# Decoder_relay_4bit_Compact_REV_0.net
KiCad netlist of a schematic drawn in EAGLE
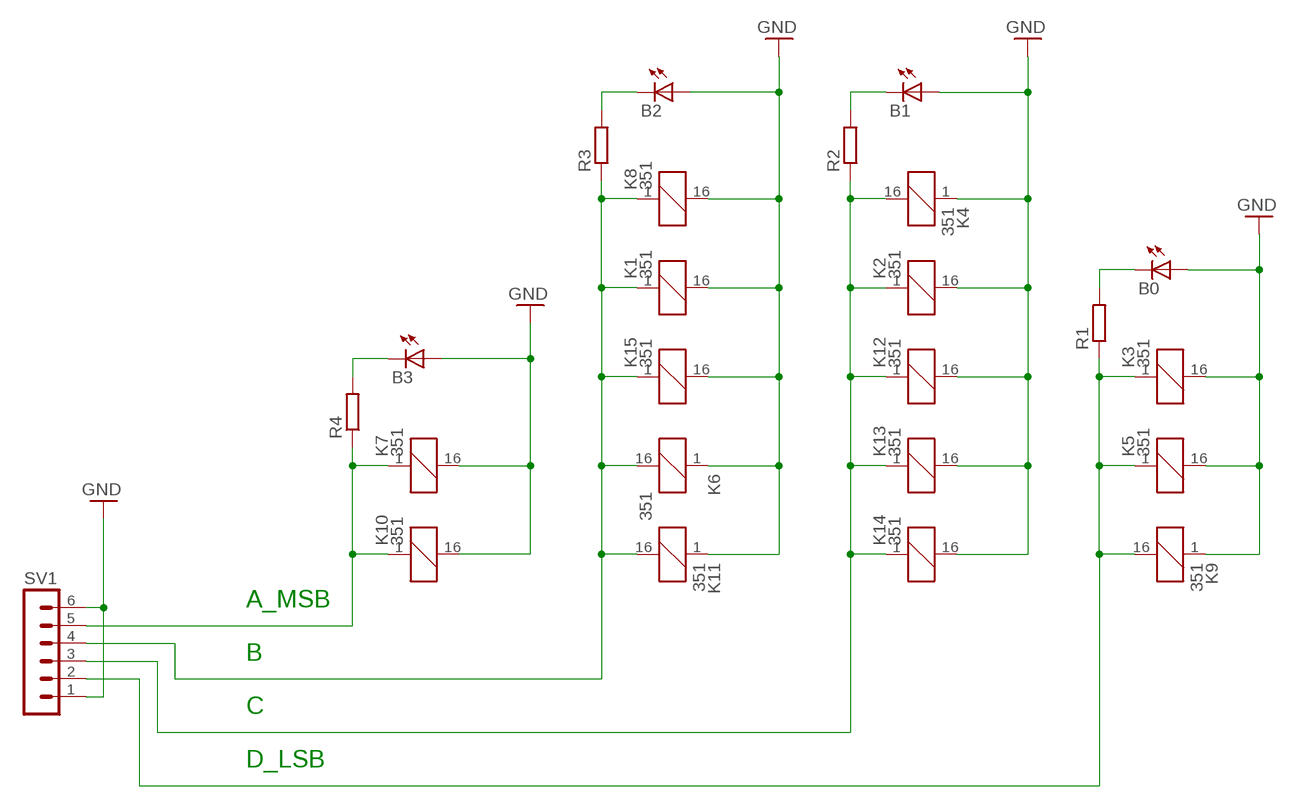
[diagram p0: schematic, sheet 1, part 1 of 2]
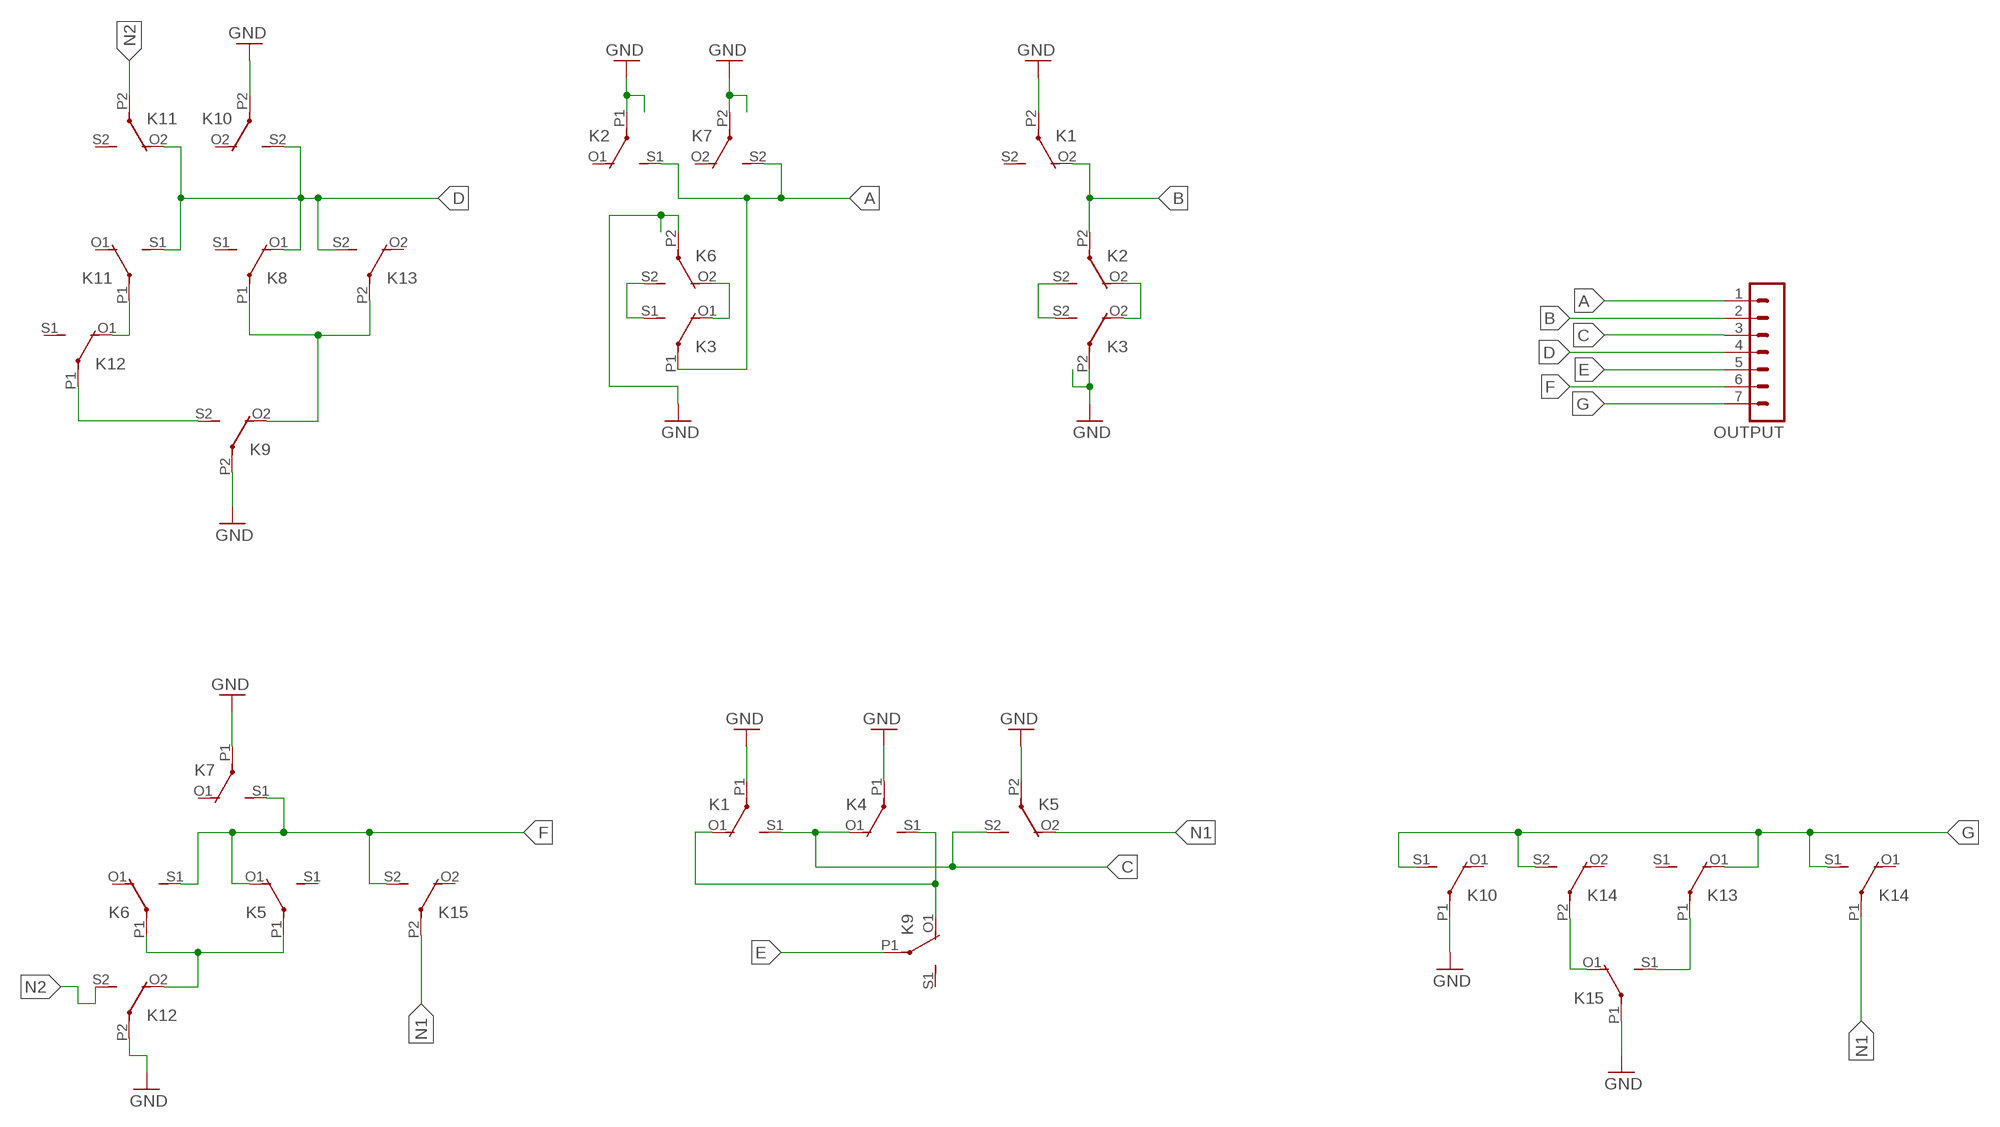
[diagram p1: schematic, sheet 1, part 2 of 2]

(export (version "E")
  (design (tool "Eeschema 10.0.6"))
  (components
    (comp (ref "B0")
      (value "LED3MM")
      (footprint "eagle-import:LED3MM")
      (libsource (lib "eagle-import") (part "LED3MM"))
    )
    (comp (ref "B1")
      (value "LED3MM")
      (footprint "eagle-import:LED3MM")
      (libsource (lib "eagle-import") (part "LED3MM"))
    )
    (comp (ref "B2")
      (value "LED3MM")
      (footprint "eagle-import:LED3MM")
      (libsource (lib "eagle-import") (part "LED3MM"))
    )
    (comp (ref "B3")
      (value "LED3MM")
      (footprint "eagle-import:LED3MM")
      (libsource (lib "eagle-import") (part "LED3MM"))
    )
    (comp (ref "K1")
      (value "351")
      (footprint "eagle-import:351")
      (libsource (lib "eagle-import") (part "351"))
    )
    (comp (ref "K2")
      (value "351")
      (footprint "eagle-import:351")
      (libsource (lib "eagle-import") (part "351"))
    )
    (comp (ref "K3")
      (value "351")
      (footprint "eagle-import:351")
      (libsource (lib "eagle-import") (part "351"))
    )
    (comp (ref "K4")
      (value "351")
      (footprint "eagle-import:351")
      (libsource (lib "eagle-import") (part "351"))
    )
    (comp (ref "K5")
      (value "351")
      (footprint "eagle-import:351")
      (libsource (lib "eagle-import") (part "351"))
    )
    (comp (ref "K6")
      (value "351")
      (footprint "eagle-import:351")
      (libsource (lib "eagle-import") (part "351"))
    )
    (comp (ref "K7")
      (value "351")
      (footprint "eagle-import:351")
      (libsource (lib "eagle-import") (part "351"))
    )
    (comp (ref "K8")
      (value "351")
      (footprint "eagle-import:351")
      (libsource (lib "eagle-import") (part "351"))
    )
    (comp (ref "K9")
      (value "351")
      (footprint "eagle-import:351")
      (libsource (lib "eagle-import") (part "351"))
    )
    (comp (ref "K10")
      (value "351")
      (footprint "eagle-import:351")
      (libsource (lib "eagle-import") (part "351"))
    )
    (comp (ref "K11")
      (value "351")
      (footprint "eagle-import:351")
      (libsource (lib "eagle-import") (part "351"))
    )
    (comp (ref "K12")
      (value "351")
      (footprint "eagle-import:351")
      (libsource (lib "eagle-import") (part "351"))
    )
    (comp (ref "K13")
      (value "351")
      (footprint "eagle-import:351")
      (libsource (lib "eagle-import") (part "351"))
    )
    (comp (ref "K14")
      (value "351")
      (footprint "eagle-import:351")
      (libsource (lib "eagle-import") (part "351"))
    )
    (comp (ref "K15")
      (value "351")
      (footprint "eagle-import:351")
      (libsource (lib "eagle-import") (part "351"))
    )
    (comp (ref "OUTPUT")
      (value "MA07-1")
      (footprint "eagle-import:MA07-1")
      (libsource (lib "eagle-import") (part "MA07-1"))
    )
    (comp (ref "R1")
      (value "R-EU_M0805")
      (footprint "eagle-import:M0805")
      (libsource (lib "eagle-import") (part "R-EU_M0805"))
    )
    (comp (ref "R2")
      (value "R-EU_M0805")
      (footprint "eagle-import:M0805")
      (libsource (lib "eagle-import") (part "R-EU_M0805"))
    )
    (comp (ref "R3")
      (value "R-EU_M0805")
      (footprint "eagle-import:M0805")
      (libsource (lib "eagle-import") (part "R-EU_M0805"))
    )
    (comp (ref "R4")
      (value "R-EU_M0805")
      (footprint "eagle-import:M0805")
      (libsource (lib "eagle-import") (part "R-EU_M0805"))
    )
    (comp (ref "SV1")
      (value "MA06-1")
      (footprint "eagle-import:MA06-1")
      (libsource (lib "eagle-import") (part "MA06-1"))
    )
  )
  (nets
    (net (code "1") (name "A") (class "Default")
      (node (ref "K2") (pin "S1") (pinfunction "S_S1") (pintype "passive"))
      (node (ref "K3") (pin "P1") (pinfunction "P_P1") (pintype "passive"))
      (node (ref "K7") (pin "S2") (pinfunction "S_S2") (pintype "passive"))
      (node (ref "OUTPUT") (pin "1") (pinfunction "1_1") (pintype "passive"))
    )
    (net (code "2") (name "B") (class "Default")
      (node (ref "K1") (pin "O2") (pinfunction "O_O2") (pintype "passive"))
      (node (ref "K2") (pin "P2") (pinfunction "P_P2") (pintype "passive"))
      (node (ref "OUTPUT") (pin "2") (pinfunction "2_2") (pintype "passive"))
    )
    (net (code "3") (name "C") (class "Default")
      (node (ref "K1") (pin "S1") (pinfunction "S_S1") (pintype "passive"))
      (node (ref "K4") (pin "O1") (pinfunction "O_O1") (pintype "passive"))
      (node (ref "K5") (pin "S2") (pinfunction "S_S2") (pintype "passive"))
      (node (ref "OUTPUT") (pin "3") (pinfunction "3_3") (pintype "passive"))
    )
    (net (code "4") (name "D") (class "Default")
      (node (ref "K10") (pin "S2") (pinfunction "S_S2") (pintype "passive"))
      (node (ref "K11") (pin "O2") (pinfunction "O_O2") (pintype "passive"))
      (node (ref "K11") (pin "S1") (pinfunction "S_S1") (pintype "passive"))
      (node (ref "K13") (pin "S2") (pinfunction "S_S2") (pintype "passive"))
      (node (ref "K8") (pin "O1") (pinfunction "O_O1") (pintype "passive"))
      (node (ref "OUTPUT") (pin "4") (pinfunction "4_4") (pintype "passive"))
    )
    (net (code "5") (name "E") (class "Default")
      (node (ref "K9") (pin "P1") (pinfunction "P_P1") (pintype "passive"))
      (node (ref "OUTPUT") (pin "5") (pinfunction "5_5") (pintype "passive"))
    )
    (net (code "6") (name "F") (class "Default")
      (node (ref "K15") (pin "S2") (pinfunction "S_S2") (pintype "passive"))
      (node (ref "K5") (pin "O1") (pinfunction "O_O1") (pintype "passive"))
      (node (ref "K6") (pin "S1") (pinfunction "S_S1") (pintype "passive"))
      (node (ref "K7") (pin "S1") (pinfunction "S_S1") (pintype "passive"))
      (node (ref "OUTPUT") (pin "6") (pinfunction "6_6") (pintype "passive"))
    )
    (net (code "7") (name "G") (class "Default")
      (node (ref "K10") (pin "S1") (pinfunction "S_S1") (pintype "passive"))
      (node (ref "K13") (pin "O1") (pinfunction "O_O1") (pintype "passive"))
      (node (ref "K14") (pin "S1") (pinfunction "S_S1") (pintype "passive"))
      (node (ref "K14") (pin "S2") (pinfunction "S_S2") (pintype "passive"))
      (node (ref "OUTPUT") (pin "7") (pinfunction "7_7") (pintype "passive"))
    )
    (net (code "8") (name "GND") (class "Default")
      (node (ref "B0") (pin "A") (pinfunction "A_A") (pintype "passive"))
      (node (ref "B1") (pin "A") (pinfunction "A_A") (pintype "passive"))
      (node (ref "B2") (pin "A") (pinfunction "A_A") (pintype "passive"))
      (node (ref "B3") (pin "A") (pinfunction "A_A") (pintype "passive"))
      (node (ref "K1") (pin "16") (pinfunction "2_16") (pintype "passive"))
      (node (ref "K1") (pin "P1") (pinfunction "P_P1") (pintype "passive"))
      (node (ref "K1") (pin "P2") (pinfunction "P_P2") (pintype "passive"))
      (node (ref "K10") (pin "16") (pinfunction "2_16") (pintype "passive"))
      (node (ref "K10") (pin "P1") (pinfunction "P_P1") (pintype "passive"))
      (node (ref "K10") (pin "P2") (pinfunction "P_P2") (pintype "passive"))
      (node (ref "K11") (pin "1") (pinfunction "1_1") (pintype "passive"))
      (node (ref "K12") (pin "16") (pinfunction "2_16") (pintype "passive"))
      (node (ref "K12") (pin "P2") (pinfunction "P_P2") (pintype "passive"))
      (node (ref "K13") (pin "16") (pinfunction "2_16") (pintype "passive"))
      (node (ref "K14") (pin "16") (pinfunction "2_16") (pintype "passive"))
      (node (ref "K15") (pin "16") (pinfunction "2_16") (pintype "passive"))
      (node (ref "K15") (pin "P1") (pinfunction "P_P1") (pintype "passive"))
      (node (ref "K2") (pin "16") (pinfunction "2_16") (pintype "passive"))
      (node (ref "K2") (pin "P1") (pinfunction "P_P1") (pintype "passive"))
      (node (ref "K3") (pin "16") (pinfunction "2_16") (pintype "passive"))
      (node (ref "K3") (pin "P2") (pinfunction "P_P2") (pintype "passive"))
      (node (ref "K4") (pin "1") (pinfunction "1_1") (pintype "passive"))
      (node (ref "K4") (pin "P1") (pinfunction "P_P1") (pintype "passive"))
      (node (ref "K5") (pin "16") (pinfunction "2_16") (pintype "passive"))
      (node (ref "K5") (pin "P2") (pinfunction "P_P2") (pintype "passive"))
      (node (ref "K6") (pin "1") (pinfunction "1_1") (pintype "passive"))
      (node (ref "K6") (pin "P2") (pinfunction "P_P2") (pintype "passive"))
      (node (ref "K7") (pin "16") (pinfunction "2_16") (pintype "passive"))
      (node (ref "K7") (pin "P1") (pinfunction "P_P1") (pintype "passive"))
      (node (ref "K7") (pin "P2") (pinfunction "P_P2") (pintype "passive"))
      (node (ref "K8") (pin "16") (pinfunction "2_16") (pintype "passive"))
      (node (ref "K9") (pin "1") (pinfunction "1_1") (pintype "passive"))
      (node (ref "K9") (pin "P2") (pinfunction "P_P2") (pintype "passive"))
      (node (ref "SV1") (pin "1") (pinfunction "1_1") (pintype "passive"))
      (node (ref "SV1") (pin "6") (pinfunction "6_6") (pintype "passive"))
    )
    (net (code "9") (name "N1") (class "Default")
      (node (ref "K14") (pin "P1") (pinfunction "P_P1") (pintype "passive"))
      (node (ref "K15") (pin "P2") (pinfunction "P_P2") (pintype "passive"))
      (node (ref "K5") (pin "O2") (pinfunction "O_O2") (pintype "passive"))
    )
    (net (code "10") (name "N2") (class "Default")
      (node (ref "K11") (pin "P2") (pinfunction "P_P2") (pintype "passive"))
      (node (ref "K12") (pin "S2") (pinfunction "S_S2") (pintype "passive"))
    )
    (net (code "11") (name "Net-(B0-C)") (class "Default")
      (node (ref "B0") (pin "K") (pinfunction "C_K") (pintype "passive"))
      (node (ref "R1") (pin "2") (pinfunction "2_2") (pintype "passive"))
    )
    (net (code "12") (name "Net-(B1-C)") (class "Default")
      (node (ref "B1") (pin "K") (pinfunction "C_K") (pintype "passive"))
      (node (ref "R2") (pin "2") (pinfunction "2_2") (pintype "passive"))
    )
    (net (code "13") (name "Net-(B2-C)") (class "Default")
      (node (ref "B2") (pin "K") (pinfunction "C_K") (pintype "passive"))
      (node (ref "R3") (pin "2") (pinfunction "2_2") (pintype "passive"))
    )
    (net (code "14") (name "Net-(B3-C)") (class "Default")
      (node (ref "B3") (pin "K") (pinfunction "C_K") (pintype "passive"))
      (node (ref "R4") (pin "2") (pinfunction "2_2") (pintype "passive"))
    )
    (net (code "15") (name "Net-(K1B-O)") (class "Default")
      (node (ref "K1") (pin "O1") (pinfunction "O_O1") (pintype "passive"))
      (node (ref "K4") (pin "S1") (pinfunction "S_S1") (pintype "passive"))
      (node (ref "K9") (pin "O1") (pinfunction "O_O1") (pintype "passive"))
    )
    (net (code "16") (name "Net-(K2C-O)") (class "Default")
      (node (ref "K2") (pin "O2") (pinfunction "O_O2") (pintype "passive"))
      (node (ref "K3") (pin "O2") (pinfunction "O_O2") (pintype "passive"))
    )
    (net (code "17") (name "Net-(K2C-S)") (class "Default")
      (node (ref "K2") (pin "S2") (pinfunction "S_S2") (pintype "passive"))
      (node (ref "K3") (pin "S2") (pinfunction "S_S2") (pintype "passive"))
    )
    (net (code "18") (name "Net-(K3B-O)") (class "Default")
      (node (ref "K3") (pin "O1") (pinfunction "O_O1") (pintype "passive"))
      (node (ref "K6") (pin "O2") (pinfunction "O_O2") (pintype "passive"))
    )
    (net (code "19") (name "Net-(K3B-S)") (class "Default")
      (node (ref "K3") (pin "S1") (pinfunction "S_S1") (pintype "passive"))
      (node (ref "K6") (pin "S2") (pinfunction "S_S2") (pintype "passive"))
    )
    (net (code "20") (name "Net-(K4A-2)") (class "Default")
      (node (ref "K12") (pin "1") (pinfunction "1_1") (pintype "passive"))
      (node (ref "K13") (pin "1") (pinfunction "1_1") (pintype "passive"))
      (node (ref "K14") (pin "1") (pinfunction "1_1") (pintype "passive"))
      (node (ref "K2") (pin "1") (pinfunction "1_1") (pintype "passive"))
      (node (ref "K4") (pin "16") (pinfunction "2_16") (pintype "passive"))
      (node (ref "R2") (pin "1") (pinfunction "1_1") (pintype "passive"))
      (node (ref "SV1") (pin "3") (pinfunction "3_3") (pintype "passive"))
    )
    (net (code "21") (name "Net-(K9A-2)") (class "Default")
      (node (ref "K3") (pin "1") (pinfunction "1_1") (pintype "passive"))
      (node (ref "K5") (pin "1") (pinfunction "1_1") (pintype "passive"))
      (node (ref "K9") (pin "16") (pinfunction "2_16") (pintype "passive"))
      (node (ref "R1") (pin "1") (pinfunction "1_1") (pintype "passive"))
      (node (ref "SV1") (pin "2") (pinfunction "2_2") (pintype "passive"))
    )
    (net (code "22") (name "Net-(K10-Pad1)") (class "Default")
      (node (ref "K10") (pin "1") (pinfunction "1_1") (pintype "passive"))
      (node (ref "K7") (pin "1") (pinfunction "1_1") (pintype "passive"))
      (node (ref "R4") (pin "1") (pinfunction "1_1") (pintype "passive"))
      (node (ref "SV1") (pin "5") (pinfunction "5_5") (pintype "passive"))
    )
    (net (code "23") (name "Net-(K11A-2)") (class "Default")
      (node (ref "K1") (pin "1") (pinfunction "1_1") (pintype "passive"))
      (node (ref "K11") (pin "16") (pinfunction "2_16") (pintype "passive"))
      (node (ref "K15") (pin "1") (pinfunction "1_1") (pintype "passive"))
      (node (ref "K6") (pin "16") (pinfunction "2_16") (pintype "passive"))
      (node (ref "K8") (pin "1") (pinfunction "1_1") (pintype "passive"))
      (node (ref "R3") (pin "1") (pinfunction "1_1") (pintype "passive"))
      (node (ref "SV1") (pin "4") (pinfunction "4_4") (pintype "passive"))
    )
    (net (code "24") (name "Net-(K11B-P)") (class "Default")
      (node (ref "K11") (pin "P1") (pinfunction "P_P1") (pintype "passive"))
      (node (ref "K12") (pin "O1") (pinfunction "O_O1") (pintype "passive"))
    )
    (net (code "25") (name "Net-(K12B-P)") (class "Default")
      (node (ref "K12") (pin "P1") (pinfunction "P_P1") (pintype "passive"))
      (node (ref "K9") (pin "S2") (pinfunction "S_S2") (pintype "passive"))
    )
    (net (code "26") (name "Net-(K12C-O)") (class "Default")
      (node (ref "K12") (pin "O2") (pinfunction "O_O2") (pintype "passive"))
      (node (ref "K5") (pin "P1") (pinfunction "P_P1") (pintype "passive"))
      (node (ref "K6") (pin "P1") (pinfunction "P_P1") (pintype "passive"))
    )
    (net (code "27") (name "Net-(K13B-P)") (class "Default")
      (node (ref "K13") (pin "P1") (pinfunction "P_P1") (pintype "passive"))
      (node (ref "K15") (pin "S1") (pinfunction "S_S1") (pintype "passive"))
    )
    (net (code "28") (name "Net-(K13C-P)") (class "Default")
      (node (ref "K13") (pin "P2") (pinfunction "P_P2") (pintype "passive"))
      (node (ref "K8") (pin "P1") (pinfunction "P_P1") (pintype "passive"))
      (node (ref "K9") (pin "O2") (pinfunction "O_O2") (pintype "passive"))
    )
    (net (code "29") (name "Net-(K14C-P)") (class "Default")
      (node (ref "K14") (pin "P2") (pinfunction "P_P2") (pintype "passive"))
      (node (ref "K15") (pin "O1") (pinfunction "O_O1") (pintype "passive"))
    )
    (net (code "30") (name "unconnected-(K1C-S-PadS2)") (class "Default")
      (node (ref "K1") (pin "S2") (pinfunction "S_S2") (pintype "passive"))
    )
    (net (code "31") (name "unconnected-(K2B-O-PadO1)") (class "Default")
      (node (ref "K2") (pin "O1") (pinfunction "O_O1") (pintype "passive"))
    )
    (net (code "32") (name "unconnected-(K5B-S-PadS1)") (class "Default")
      (node (ref "K5") (pin "S1") (pinfunction "S_S1") (pintype "passive"))
    )
    (net (code "33") (name "unconnected-(K6B-O-PadO1)") (class "Default")
      (node (ref "K6") (pin "O1") (pinfunction "O_O1") (pintype "passive"))
    )
    (net (code "34") (name "unconnected-(K7B-O-PadO1)") (class "Default")
      (node (ref "K7") (pin "O1") (pinfunction "O_O1") (pintype "passive"))
    )
    (net (code "35") (name "unconnected-(K7C-O-PadO2)") (class "Default")
      (node (ref "K7") (pin "O2") (pinfunction "O_O2") (pintype "passive"))
    )
    (net (code "36") (name "unconnected-(K8B-S-PadS1)") (class "Default")
      (node (ref "K8") (pin "S1") (pinfunction "S_S1") (pintype "passive"))
    )
    (net (code "37") (name "unconnected-(K9B-S-PadS1)") (class "Default")
      (node (ref "K9") (pin "S1") (pinfunction "S_S1") (pintype "passive"))
    )
    (net (code "38") (name "unconnected-(K10B-O-PadO1)") (class "Default")
      (node (ref "K10") (pin "O1") (pinfunction "O_O1") (pintype "passive"))
    )
    (net (code "39") (name "unconnected-(K10C-O-PadO2)") (class "Default")
      (node (ref "K10") (pin "O2") (pinfunction "O_O2") (pintype "passive"))
    )
    (net (code "40") (name "unconnected-(K11B-O-PadO1)") (class "Default")
      (node (ref "K11") (pin "O1") (pinfunction "O_O1") (pintype "passive"))
    )
    (net (code "41") (name "unconnected-(K11C-S-PadS2)") (class "Default")
      (node (ref "K11") (pin "S2") (pinfunction "S_S2") (pintype "passive"))
    )
    (net (code "42") (name "unconnected-(K12B-S-PadS1)") (class "Default")
      (node (ref "K12") (pin "S1") (pinfunction "S_S1") (pintype "passive"))
    )
    (net (code "43") (name "unconnected-(K13B-S-PadS1)") (class "Default")
      (node (ref "K13") (pin "S1") (pinfunction "S_S1") (pintype "passive"))
    )
    (net (code "44") (name "unconnected-(K13C-O-PadO2)") (class "Default")
      (node (ref "K13") (pin "O2") (pinfunction "O_O2") (pintype "passive"))
    )
    (net (code "45") (name "unconnected-(K14B-O-PadO1)") (class "Default")
      (node (ref "K14") (pin "O1") (pinfunction "O_O1") (pintype "passive"))
    )
    (net (code "46") (name "unconnected-(K14C-O-PadO2)") (class "Default")
      (node (ref "K14") (pin "O2") (pinfunction "O_O2") (pintype "passive"))
    )
    (net (code "47") (name "unconnected-(K15C-O-PadO2)") (class "Default")
      (node (ref "K15") (pin "O2") (pinfunction "O_O2") (pintype "passive"))
    )
  )
)
